# QuadDeckV2.net
KiCad netlist of a schematic drawn in Altium Designer
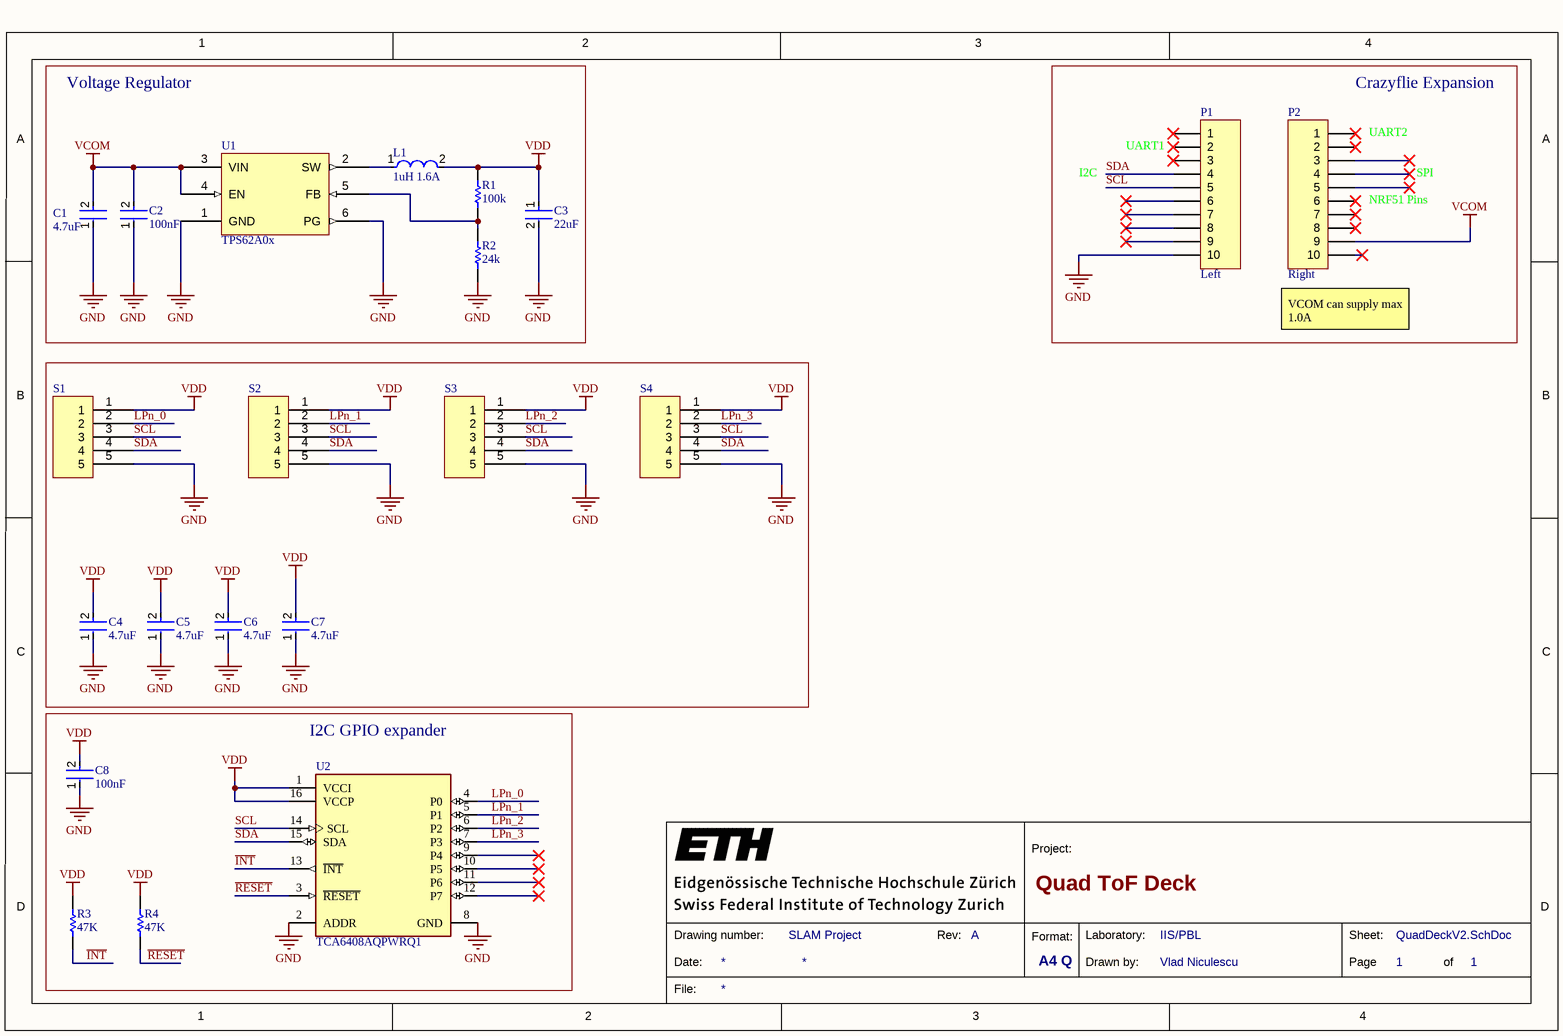
[diagram p0: QuadDeckV2.SchDoc]

(export (version "E")
  (design (tool "Eeschema 10.0.6"))
  (components
    (comp (ref "C1")
      (value "4.7uF")
      (footprint "FP-GRM188-0_1-MFG")
      (description "CAP CER 4.7UF 6.3V X5R 0603")
      (fields (field (name "VOLTAGE") "6.3V") (field (name "TOLERANCE") "10%"))
      (libsource (lib "Altium Content Vault") (part "236180d848d6139a670b325ea6854c9"))
    )
    (comp (ref "C2")
      (value "100nF")
      (footprint "FP-GRM15-MFG")
      (description "CAP CER 0.1UF 16V X7R 0402")
      (fields (field (name "MANUFACTURER PART NUMBER") "GRM155R71C104KA88D") (field (name "TOLERANCE") "10%"))
      (libsource (lib "Altium Content Vault") (part "236180d848d6139a670b325ea6854c9"))
    )
    (comp (ref "C3")
      (value "22uF")
      (footprint "FP-GRM21B-0_15-MFG")
      (description "Chip Multilayer Ceramic Capacitors for General Purpose, 0805, 22uF, X5R, 15%, 20%, 6.3V")
      (fields (field (name "VOLTAGE") "6.3V") (field (name "TOLERANCE") "20%"))
      (libsource (lib "Altium Content Vault") (part "b4654b650e69147ec39a6b967a45e02"))
    )
    (comp (ref "C4")
      (value "4.7uF")
      (footprint "FP-GRM188-0_1-MFG")
      (description "CAP CER 4.7UF 6.3V X5R 0603")
      (fields (field (name "VOLTAGE") "6.3V") (field (name "TOLERANCE") "10%"))
      (libsource (lib "Altium Content Vault") (part "236180d848d6139a670b325ea6854c9"))
    )
    (comp (ref "C5")
      (value "4.7uF")
      (footprint "FP-GRM188-0_1-MFG")
      (description "CAP CER 4.7UF 6.3V X5R 0603")
      (fields (field (name "VOLTAGE") "6.3V") (field (name "TOLERANCE") "10%"))
      (libsource (lib "Altium Content Vault") (part "236180d848d6139a670b325ea6854c9"))
    )
    (comp (ref "C6")
      (value "4.7uF")
      (footprint "FP-GRM188-0_1-MFG")
      (description "CAP CER 4.7UF 6.3V X5R 0603")
      (fields (field (name "VOLTAGE") "6.3V") (field (name "TOLERANCE") "10%"))
      (libsource (lib "Altium Content Vault") (part "236180d848d6139a670b325ea6854c9"))
    )
    (comp (ref "C7")
      (value "4.7uF")
      (footprint "FP-GRM188-0_1-MFG")
      (description "CAP CER 4.7UF 6.3V X5R 0603")
      (fields (field (name "VOLTAGE") "6.3V") (field (name "TOLERANCE") "10%"))
      (libsource (lib "Altium Content Vault") (part "236180d848d6139a670b325ea6854c9"))
    )
    (comp (ref "C8")
      (value "100nF")
      (footprint "FP-GRM15-MFG")
      (description "CAP CER 0.1UF 16V X7R 0402")
      (fields (field (name "MANUFACTURER PART NUMBER") "GRM155R71C104KA88D") (field (name "TOLERANCE") "10%"))
      (libsource (lib "Altium Content Vault") (part "236180d848d6139a670b325ea6854c9"))
    )
    (comp (ref "L1")
      (value "1uH 1.6A")
      (footprint "FP-LQM21PN_EH-w1_5-IPC_A")
      (description "FIXED IND 1UH 1.6A 107 MOHM SMD")
      (fields (field (name "TOLERANCE") "20%"))
      (libsource (lib "Altium Content Vault") (part "725321dda6339637d4d059423bc1c3c"))
    )
    (comp (ref "P1")
      (value "Left")
      (footprint "crazyflie-header:PCBComponent_1")
      (description "Header, 10-Pin")
      (fields (field (name "PUBLISHER") "Altium Limited"))
      (libsource (lib "") (part "MHDR1X10_1"))
    )
    (comp (ref "P2")
      (value "Right")
      (footprint "crazyflie-header:PCBComponent_1")
      (description "Header, 10-Pin")
      (fields (field (name "PUBLISHER") "Altium Limited"))
      (libsource (lib "Miscellaneous Connectors") (part "MHDR1X10"))
    )
    (comp (ref "R1")
      (value "100k")
      (footprint "RESC1608X55X30ML20T20")
      (fields (field (name "PART NUMBER") "ERA3AEB104V") (field (name "MANUFACTURER") "Panasonic"))
      (libsource (lib "Altium Content Vault") (part "RES"))
    )
    (comp (ref "R2")
      (value "24k")
      (footprint "RESC0603(1608)_N")
      (description "24K 0.1W 5% 0603 (1608 Metric)  SMD")
      (fields (field (name "TOLERANCE") "5 %") (field (name "POWER") "0.1 W"))
      (libsource (lib "Altium Content Vault") (part "RES"))
    )
    (comp (ref "R3")
      (value "47K")
      (footprint "RESC1608X55X30NL15T15")
      (description "Chip Resistor, 47 KOhm, +/- 1%, 0.1 W, -55 to 155 degC, 0603 (1608 Metric), RoHS, Tape and Reel")
      (libsource (lib "Altium Content Vault") (part "RES-2"))
    )
    (comp (ref "R4")
      (value "47K")
      (footprint "RESC1608X55X30NL15T15")
      (description "Chip Resistor, 47 KOhm, +/- 1%, 0.1 W, -55 to 155 degC, 0603 (1608 Metric), RoHS, Tape and Reel")
      (libsource (lib "Altium Content Vault") (part "RES-2"))
    )
    (comp (ref "S1")
      (value "Component_1")
      (footprint "tof-connector-5:tof-connector")
      (libsource (lib "tof-connector-5") (part "Component_1"))
    )
    (comp (ref "S2")
      (value "Component_1")
      (footprint "tof-connector-5:tof-connector")
      (libsource (lib "tof-connector-5") (part "Component_1"))
    )
    (comp (ref "S3")
      (value "Component_1")
      (footprint "tof-connector-5:tof-connector")
      (libsource (lib "tof-connector-5") (part "Component_1"))
    )
    (comp (ref "S4")
      (value "Component_1")
      (footprint "tof-connector-5:tof-connector")
      (libsource (lib "tof-connector-5") (part "Component_1"))
    )
    (comp (ref "U1")
      (value "TPS62A0x")
      (footprint "SOT50P245X110-6N")
      (libsource (lib "TPS62A01") (part "TPS62A01"))
    )
    (comp (ref "U2")
      (value "TCA6408AQPWRQ1")
      (footprint "FP-PW0016A-IPC_B")
      (description "IC I/O EXPANDER I2C 8B 16TSSOP")
      (libsource (lib "Altium Content Vault") (part "945f262353ccef2f090be9ef51e4a3e"))
    )
  )
  (nets
    (net (code "1") (name "/INT") (class "Default")
      (node (ref "R3") (pin "1") (pinfunction "1_1") (pintype "passive"))
      (node (ref "U2") (pin "13") (pinfunction "~{INT}_13") (pintype "output"))
    )
    (net (code "2") (name "/LPn_0") (class "Default")
      (node (ref "S1") (pin "2") (pinfunction "2_2") (pintype "passive"))
      (node (ref "U2") (pin "4") (pinfunction "P0_4") (pintype "bidirectional"))
    )
    (net (code "3") (name "/LPn_1") (class "Default")
      (node (ref "S2") (pin "2") (pinfunction "2_2") (pintype "passive"))
      (node (ref "U2") (pin "5") (pinfunction "P1_5") (pintype "bidirectional"))
    )
    (net (code "4") (name "/LPn_2") (class "Default")
      (node (ref "S3") (pin "2") (pinfunction "2_2") (pintype "passive"))
      (node (ref "U2") (pin "6") (pinfunction "P2_6") (pintype "bidirectional"))
    )
    (net (code "5") (name "/LPn_3") (class "Default")
      (node (ref "S4") (pin "2") (pinfunction "2_2") (pintype "passive"))
      (node (ref "U2") (pin "7") (pinfunction "P3_7") (pintype "bidirectional"))
    )
    (net (code "6") (name "/RESET") (class "Default")
      (node (ref "R4") (pin "1") (pinfunction "1_1") (pintype "passive"))
      (node (ref "U2") (pin "3") (pinfunction "~{RESET}_3") (pintype "input"))
    )
    (net (code "7") (name "/SCL") (class "Default")
      (node (ref "P1") (pin "5") (pinfunction "5_5") (pintype "passive"))
      (node (ref "S1") (pin "3") (pinfunction "3_3") (pintype "passive"))
      (node (ref "S2") (pin "3") (pinfunction "3_3") (pintype "passive"))
      (node (ref "S3") (pin "3") (pinfunction "3_3") (pintype "passive"))
      (node (ref "S4") (pin "3") (pinfunction "3_3") (pintype "passive"))
      (node (ref "U2") (pin "14") (pinfunction "SCL_14") (pintype "input"))
    )
    (net (code "8") (name "/SDA") (class "Default")
      (node (ref "P1") (pin "4") (pinfunction "4_4") (pintype "passive"))
      (node (ref "S1") (pin "4") (pinfunction "4_4") (pintype "passive"))
      (node (ref "S2") (pin "4") (pinfunction "4_4") (pintype "passive"))
      (node (ref "S3") (pin "4") (pinfunction "4_4") (pintype "passive"))
      (node (ref "S4") (pin "4") (pinfunction "4_4") (pintype "passive"))
      (node (ref "U2") (pin "15") (pinfunction "SDA_15") (pintype "bidirectional"))
    )
    (net (code "9") (name "GND") (class "Default")
      (node (ref "C1") (pin "1") (pinfunction "1_1") (pintype "passive"))
      (node (ref "C2") (pin "1") (pinfunction "1_1") (pintype "passive"))
      (node (ref "C3") (pin "2") (pinfunction "2_2") (pintype "passive"))
      (node (ref "C4") (pin "1") (pinfunction "1_1") (pintype "passive"))
      (node (ref "C5") (pin "1") (pinfunction "1_1") (pintype "passive"))
      (node (ref "C6") (pin "1") (pinfunction "1_1") (pintype "passive"))
      (node (ref "C7") (pin "1") (pinfunction "1_1") (pintype "passive"))
      (node (ref "C8") (pin "1") (pinfunction "1_1") (pintype "passive"))
      (node (ref "P1") (pin "10") (pinfunction "10_10") (pintype "passive"))
      (node (ref "R2") (pin "1") (pinfunction "1_1") (pintype "passive"))
      (node (ref "S1") (pin "5") (pinfunction "5_5") (pintype "passive"))
      (node (ref "S2") (pin "5") (pinfunction "5_5") (pintype "passive"))
      (node (ref "S3") (pin "5") (pinfunction "5_5") (pintype "passive"))
      (node (ref "S4") (pin "5") (pinfunction "5_5") (pintype "passive"))
      (node (ref "U1") (pin "1") (pinfunction "GND_1") (pintype "passive"))
      (node (ref "U1") (pin "6") (pinfunction "PG_6") (pintype "output"))
      (node (ref "U2") (pin "2") (pinfunction "ADDR_2") (pintype "power_in"))
      (node (ref "U2") (pin "8") (pinfunction "GND_8") (pintype "power_in"))
    )
    (net (code "10") (name "Net-(U1-FB)") (class "Default")
      (node (ref "R1") (pin "1") (pinfunction "1_1") (pintype "passive"))
      (node (ref "R2") (pin "2") (pinfunction "2_2") (pintype "passive"))
      (node (ref "U1") (pin "5") (pinfunction "FB_5") (pintype "input"))
    )
    (net (code "11") (name "Net-(U1-SW)") (class "Default")
      (node (ref "L1") (pin "1") (pinfunction "1_1") (pintype "passive"))
      (node (ref "U1") (pin "2") (pinfunction "SW_2") (pintype "output"))
    )
    (net (code "12") (name "VCOM") (class "Default")
      (node (ref "C1") (pin "2") (pinfunction "2_2") (pintype "passive"))
      (node (ref "C2") (pin "2") (pinfunction "2_2") (pintype "passive"))
      (node (ref "P2") (pin "9") (pinfunction "9_9") (pintype "passive"))
      (node (ref "U1") (pin "3") (pinfunction "VIN_3") (pintype "power_in"))
      (node (ref "U1") (pin "4") (pinfunction "EN_4") (pintype "input"))
    )
    (net (code "13") (name "VDD") (class "Default")
      (node (ref "C3") (pin "1") (pinfunction "1_1") (pintype "passive"))
      (node (ref "C4") (pin "2") (pinfunction "2_2") (pintype "passive"))
      (node (ref "C5") (pin "2") (pinfunction "2_2") (pintype "passive"))
      (node (ref "C6") (pin "2") (pinfunction "2_2") (pintype "passive"))
      (node (ref "C7") (pin "2") (pinfunction "2_2") (pintype "passive"))
      (node (ref "C8") (pin "2") (pinfunction "2_2") (pintype "passive"))
      (node (ref "L1") (pin "2") (pinfunction "2_2") (pintype "passive"))
      (node (ref "R1") (pin "2") (pinfunction "2_2") (pintype "passive"))
      (node (ref "R3") (pin "2") (pinfunction "2_2") (pintype "passive"))
      (node (ref "R4") (pin "2") (pinfunction "2_2") (pintype "passive"))
      (node (ref "S1") (pin "1") (pinfunction "1_1") (pintype "passive"))
      (node (ref "S2") (pin "1") (pinfunction "1_1") (pintype "passive"))
      (node (ref "S3") (pin "1") (pinfunction "1_1") (pintype "passive"))
      (node (ref "S4") (pin "1") (pinfunction "1_1") (pintype "passive"))
      (node (ref "U2") (pin "1") (pinfunction "VCCI_1") (pintype "power_in"))
      (node (ref "U2") (pin "16") (pinfunction "VCCP_16") (pintype "power_in"))
    )
    (net (code "14") (name "unconnected-(P1-Pad1)") (class "Default")
      (node (ref "P1") (pin "1") (pinfunction "1_1") (pintype "passive+no_connect"))
    )
    (net (code "15") (name "unconnected-(P1-Pad2)") (class "Default")
      (node (ref "P1") (pin "2") (pinfunction "2_2") (pintype "passive+no_connect"))
    )
    (net (code "16") (name "unconnected-(P1-Pad3)") (class "Default")
      (node (ref "P1") (pin "3") (pinfunction "3_3") (pintype "passive+no_connect"))
    )
    (net (code "17") (name "unconnected-(P1-Pad6)") (class "Default")
      (node (ref "P1") (pin "6") (pinfunction "6_6") (pintype "passive+no_connect"))
    )
    (net (code "18") (name "unconnected-(P1-Pad7)") (class "Default")
      (node (ref "P1") (pin "7") (pinfunction "7_7") (pintype "passive+no_connect"))
    )
    (net (code "19") (name "unconnected-(P1-Pad8)") (class "Default")
      (node (ref "P1") (pin "8") (pinfunction "8_8") (pintype "passive+no_connect"))
    )
    (net (code "20") (name "unconnected-(P1-Pad9)") (class "Default")
      (node (ref "P1") (pin "9") (pinfunction "9_9") (pintype "passive+no_connect"))
    )
    (net (code "21") (name "unconnected-(P2-Pad1)") (class "Default")
      (node (ref "P2") (pin "1") (pinfunction "1_1") (pintype "passive+no_connect"))
    )
    (net (code "22") (name "unconnected-(P2-Pad2)") (class "Default")
      (node (ref "P2") (pin "2") (pinfunction "2_2") (pintype "passive+no_connect"))
    )
    (net (code "23") (name "unconnected-(P2-Pad3)") (class "Default")
      (node (ref "P2") (pin "3") (pinfunction "3_3") (pintype "passive+no_connect"))
    )
    (net (code "24") (name "unconnected-(P2-Pad4)") (class "Default")
      (node (ref "P2") (pin "4") (pinfunction "4_4") (pintype "passive+no_connect"))
    )
    (net (code "25") (name "unconnected-(P2-Pad5)") (class "Default")
      (node (ref "P2") (pin "5") (pinfunction "5_5") (pintype "passive+no_connect"))
    )
    (net (code "26") (name "unconnected-(P2-Pad6)") (class "Default")
      (node (ref "P2") (pin "6") (pinfunction "6_6") (pintype "passive+no_connect"))
    )
    (net (code "27") (name "unconnected-(P2-Pad7)") (class "Default")
      (node (ref "P2") (pin "7") (pinfunction "7_7") (pintype "passive+no_connect"))
    )
    (net (code "28") (name "unconnected-(P2-Pad8)") (class "Default")
      (node (ref "P2") (pin "8") (pinfunction "8_8") (pintype "passive+no_connect"))
    )
    (net (code "29") (name "unconnected-(P2-Pad10)") (class "Default")
      (node (ref "P2") (pin "10") (pinfunction "10_10") (pintype "passive+no_connect"))
    )
    (net (code "30") (name "unconnected-(U2-P4-Pad9)") (class "Default")
      (node (ref "U2") (pin "9") (pinfunction "P4_9") (pintype "bidirectional+no_connect"))
    )
    (net (code "31") (name "unconnected-(U2-P5-Pad10)") (class "Default")
      (node (ref "U2") (pin "10") (pinfunction "P5_10") (pintype "bidirectional+no_connect"))
    )
    (net (code "32") (name "unconnected-(U2-P6-Pad11)") (class "Default")
      (node (ref "U2") (pin "11") (pinfunction "P6_11") (pintype "bidirectional+no_connect"))
    )
    (net (code "33") (name "unconnected-(U2-P7-Pad12)") (class "Default")
      (node (ref "U2") (pin "12") (pinfunction "P7_12") (pintype "bidirectional+no_connect"))
    )
  )
)
